# wiring.net
KiCad netlist of a schematic drawn in EAGLE
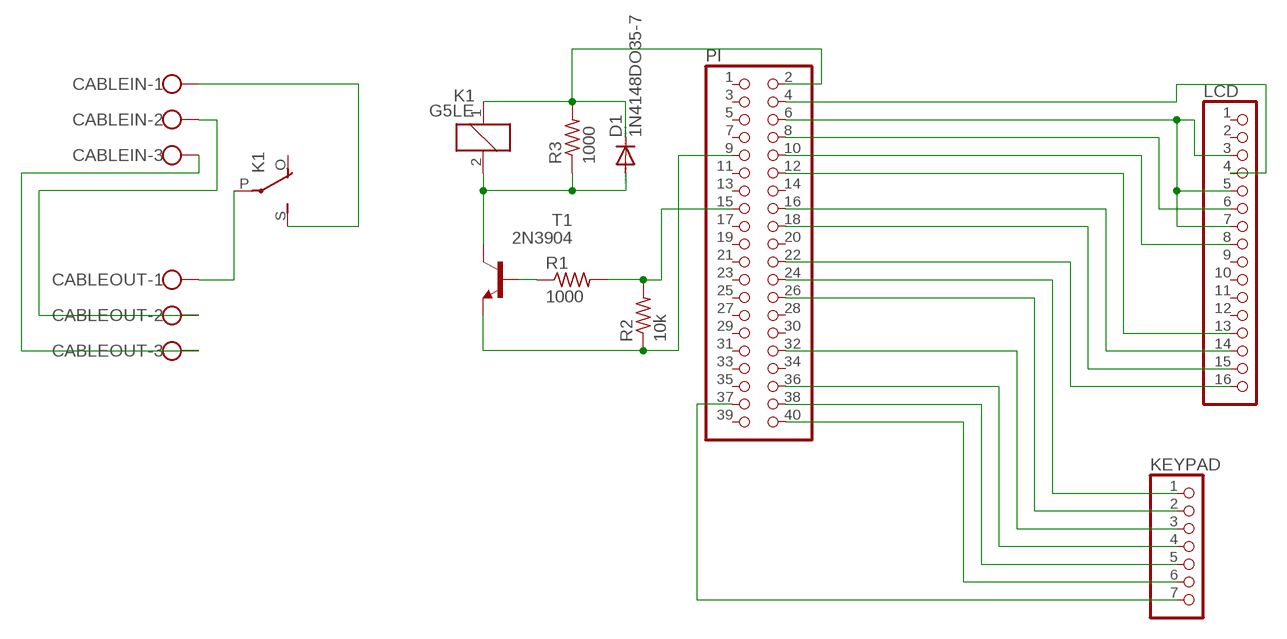
[diagram p0: schematic, sheet 1]

(export (version "E")
  (design (tool "Eeschema 10.0.6"))
  (components
    (comp (ref "CABLEIN")
      (value "W237-103")
      (footprint "eagle-import:W237-103")
      (fields (field (name "MPN") "237-103"))
      (libsource (lib "eagle-import") (part "W237-103"))
    )
    (comp (ref "CABLEOUT")
      (value "W237-103")
      (footprint "eagle-import:W237-103")
      (fields (field (name "MPN") "237-103"))
      (libsource (lib "eagle-import") (part "W237-103"))
    )
    (comp (ref "D1")
      (value "1N4148DO35-7")
      (footprint "eagle-import:DO35-7")
      (libsource (lib "eagle-import") (part "1N4148DO35-7"))
    )
    (comp (ref "K1")
      (value "G5LE")
      (footprint "eagle-import:G5LE")
      (libsource (lib "eagle-import") (part "G5LE"))
    )
    (comp (ref "KEYPAD")
      (value "PINHD-1X7")
      (footprint "eagle-import:1X07")
      (libsource (lib "eagle-import") (part "PINHD-1X7"))
    )
    (comp (ref "LCD")
      (value "PINHD-1X16")
      (footprint "eagle-import:1X16")
      (libsource (lib "eagle-import") (part "PINHD-1X16"))
    )
    (comp (ref "PI")
      (value "PINHD-2X20")
      (footprint "eagle-import:2X20")
      (libsource (lib "eagle-import") (part "PINHD-2X20"))
    )
    (comp (ref "R1")
      (value "1000")
      (footprint "eagle-import:0204_5")
      (libsource (lib "eagle-import") (part "R-US_0204/5"))
    )
    (comp (ref "R2")
      (value "10k")
      (footprint "eagle-import:0204_5")
      (libsource (lib "eagle-import") (part "R-US_0204/5"))
    )
    (comp (ref "R3")
      (value "1000")
      (footprint "eagle-import:0204_5")
      (libsource (lib "eagle-import") (part "R-US_0204/5"))
    )
    (comp (ref "T1")
      (value "2N3904")
      (footprint "eagle-import:TO92")
      (libsource (lib "eagle-import") (part "2N3904"))
    )
  )
  (nets
    (net (code "1") (name "Net-(CABLEINA-KL)") (class "Default")
      (node (ref "CABLEIN") (pin "1") (pinfunction "KL_1") (pintype "passive"))
      (node (ref "K1") (pin "S") (pinfunction "S_S") (pintype "passive"))
    )
    (net (code "2") (name "Net-(CABLEINB-KL)") (class "Default")
      (node (ref "CABLEIN") (pin "2") (pinfunction "KL_2") (pintype "passive"))
      (node (ref "CABLEOUT") (pin "2") (pinfunction "KL_2") (pintype "passive"))
    )
    (net (code "3") (name "Net-(CABLEINC-KL)") (class "Default")
      (node (ref "CABLEIN") (pin "3") (pinfunction "KL_3") (pintype "passive"))
      (node (ref "CABLEOUT") (pin "3") (pinfunction "KL_3") (pintype "passive"))
    )
    (net (code "4") (name "Net-(CABLEOUTA-KL)") (class "Default")
      (node (ref "CABLEOUT") (pin "1") (pinfunction "KL_1") (pintype "passive"))
      (node (ref "K1") (pin "P") (pinfunction "P_P") (pintype "passive"))
    )
    (net (code "5") (name "Net-(D1-PadC)") (class "Default")
      (node (ref "D1") (pin "C") (pinfunction "C_C") (pintype "passive"))
      (node (ref "K1") (pin "1") (pinfunction "1_1") (pintype "passive"))
      (node (ref "PI") (pin "2") (pinfunction "2_2") (pintype "passive"))
      (node (ref "R3") (pin "2") (pinfunction "2_2") (pintype "passive"))
    )
    (net (code "6") (name "Net-(KEYPAD-Pad1)") (class "Default")
      (node (ref "KEYPAD") (pin "1") (pinfunction "1_1") (pintype "passive"))
      (node (ref "PI") (pin "24") (pinfunction "24_24") (pintype "passive"))
    )
    (net (code "7") (name "Net-(KEYPAD-Pad2)") (class "Default")
      (node (ref "KEYPAD") (pin "2") (pinfunction "2_2") (pintype "passive"))
      (node (ref "PI") (pin "26") (pinfunction "26_26") (pintype "passive"))
    )
    (net (code "8") (name "Net-(KEYPAD-Pad3)") (class "Default")
      (node (ref "KEYPAD") (pin "3") (pinfunction "3_3") (pintype "passive"))
      (node (ref "PI") (pin "32") (pinfunction "32_32") (pintype "passive"))
    )
    (net (code "9") (name "Net-(KEYPAD-Pad4)") (class "Default")
      (node (ref "KEYPAD") (pin "4") (pinfunction "4_4") (pintype "passive"))
      (node (ref "PI") (pin "36") (pinfunction "36_36") (pintype "passive"))
    )
    (net (code "10") (name "Net-(KEYPAD-Pad5)") (class "Default")
      (node (ref "KEYPAD") (pin "5") (pinfunction "5_5") (pintype "passive"))
      (node (ref "PI") (pin "38") (pinfunction "38_38") (pintype "passive"))
    )
    (net (code "11") (name "Net-(KEYPAD-Pad6)") (class "Default")
      (node (ref "KEYPAD") (pin "6") (pinfunction "6_6") (pintype "passive"))
      (node (ref "PI") (pin "40") (pinfunction "40_40") (pintype "passive"))
    )
    (net (code "12") (name "Net-(KEYPAD-Pad7)") (class "Default")
      (node (ref "KEYPAD") (pin "7") (pinfunction "7_7") (pintype "passive"))
      (node (ref "PI") (pin "37") (pinfunction "37_37") (pintype "passive"))
    )
    (net (code "13") (name "Net-(LCD-Pad3)") (class "Default")
      (node (ref "LCD") (pin "3") (pinfunction "3_3") (pintype "passive"))
      (node (ref "LCD") (pin "5") (pinfunction "5_5") (pintype "passive"))
      (node (ref "LCD") (pin "7") (pinfunction "7_7") (pintype "passive"))
      (node (ref "PI") (pin "6") (pinfunction "6_6") (pintype "passive"))
    )
    (net (code "14") (name "Net-(LCD-Pad4)") (class "Default")
      (node (ref "LCD") (pin "4") (pinfunction "4_4") (pintype "passive"))
      (node (ref "PI") (pin "4") (pinfunction "4_4") (pintype "passive"))
    )
    (net (code "15") (name "Net-(LCD-Pad6)") (class "Default")
      (node (ref "LCD") (pin "6") (pinfunction "6_6") (pintype "passive"))
      (node (ref "PI") (pin "8") (pinfunction "8_8") (pintype "passive"))
    )
    (net (code "16") (name "Net-(LCD-Pad8)") (class "Default")
      (node (ref "LCD") (pin "8") (pinfunction "8_8") (pintype "passive"))
      (node (ref "PI") (pin "10") (pinfunction "10_10") (pintype "passive"))
    )
    (net (code "17") (name "Net-(LCD-Pad13)") (class "Default")
      (node (ref "LCD") (pin "13") (pinfunction "13_13") (pintype "passive"))
      (node (ref "PI") (pin "12") (pinfunction "12_12") (pintype "passive"))
    )
    (net (code "18") (name "Net-(LCD-Pad14)") (class "Default")
      (node (ref "LCD") (pin "14") (pinfunction "14_14") (pintype "passive"))
      (node (ref "PI") (pin "16") (pinfunction "16_16") (pintype "passive"))
    )
    (net (code "19") (name "Net-(LCD-Pad15)") (class "Default")
      (node (ref "LCD") (pin "15") (pinfunction "15_15") (pintype "passive"))
      (node (ref "PI") (pin "18") (pinfunction "18_18") (pintype "passive"))
    )
    (net (code "20") (name "Net-(LCD-Pad16)") (class "Default")
      (node (ref "LCD") (pin "16") (pinfunction "16_16") (pintype "passive"))
      (node (ref "PI") (pin "22") (pinfunction "22_22") (pintype "passive"))
    )
    (net (code "21") (name "Net-(PI-Pad15)") (class "Default")
      (node (ref "PI") (pin "15") (pinfunction "15_15") (pintype "passive"))
      (node (ref "R1") (pin "2") (pinfunction "2_2") (pintype "passive"))
      (node (ref "R2") (pin "2") (pinfunction "2_2") (pintype "passive"))
    )
    (net (code "22") (name "Net-(T1-B)") (class "Default")
      (node (ref "R1") (pin "1") (pinfunction "1_1") (pintype "passive"))
      (node (ref "T1") (pin "2") (pinfunction "B_2") (pintype "passive"))
    )
    (net (code "23") (name "Net-(T1-C)") (class "Default")
      (node (ref "D1") (pin "A") (pinfunction "A_A") (pintype "passive"))
      (node (ref "K1") (pin "2") (pinfunction "2_2") (pintype "passive"))
      (node (ref "R3") (pin "1") (pinfunction "1_1") (pintype "passive"))
      (node (ref "T1") (pin "1") (pinfunction "C_1") (pintype "passive"))
    )
    (net (code "24") (name "Net-(T1-E)") (class "Default")
      (node (ref "PI") (pin "9") (pinfunction "9_9") (pintype "passive"))
      (node (ref "R2") (pin "1") (pinfunction "1_1") (pintype "passive"))
      (node (ref "T1") (pin "3") (pinfunction "E_3") (pintype "passive"))
    )
    (net (code "25") (name "unconnected-(K1-PadO)") (class "Default")
      (node (ref "K1") (pin "O") (pinfunction "O_O") (pintype "passive"))
    )
    (net (code "26") (name "unconnected-(LCD-Pad1)") (class "Default")
      (node (ref "LCD") (pin "1") (pinfunction "1_1") (pintype "passive"))
    )
    (net (code "27") (name "unconnected-(LCD-Pad2)") (class "Default")
      (node (ref "LCD") (pin "2") (pinfunction "2_2") (pintype "passive"))
    )
    (net (code "28") (name "unconnected-(LCD-Pad9)") (class "Default")
      (node (ref "LCD") (pin "9") (pinfunction "9_9") (pintype "passive"))
    )
    (net (code "29") (name "unconnected-(LCD-Pad10)") (class "Default")
      (node (ref "LCD") (pin "10") (pinfunction "10_10") (pintype "passive"))
    )
    (net (code "30") (name "unconnected-(LCD-Pad11)") (class "Default")
      (node (ref "LCD") (pin "11") (pinfunction "11_11") (pintype "passive"))
    )
    (net (code "31") (name "unconnected-(LCD-Pad12)") (class "Default")
      (node (ref "LCD") (pin "12") (pinfunction "12_12") (pintype "passive"))
    )
    (net (code "32") (name "unconnected-(PI-Pad1)") (class "Default")
      (node (ref "PI") (pin "1") (pinfunction "1_1") (pintype "passive"))
    )
    (net (code "33") (name "unconnected-(PI-Pad3)") (class "Default")
      (node (ref "PI") (pin "3") (pinfunction "3_3") (pintype "passive"))
    )
    (net (code "34") (name "unconnected-(PI-Pad5)") (class "Default")
      (node (ref "PI") (pin "5") (pinfunction "5_5") (pintype "passive"))
    )
    (net (code "35") (name "unconnected-(PI-Pad7)") (class "Default")
      (node (ref "PI") (pin "7") (pinfunction "7_7") (pintype "passive"))
    )
    (net (code "36") (name "unconnected-(PI-Pad11)") (class "Default")
      (node (ref "PI") (pin "11") (pinfunction "11_11") (pintype "passive"))
    )
    (net (code "37") (name "unconnected-(PI-Pad13)") (class "Default")
      (node (ref "PI") (pin "13") (pinfunction "13_13") (pintype "passive"))
    )
    (net (code "38") (name "unconnected-(PI-Pad14)") (class "Default")
      (node (ref "PI") (pin "14") (pinfunction "14_14") (pintype "passive"))
    )
    (net (code "39") (name "unconnected-(PI-Pad17)") (class "Default")
      (node (ref "PI") (pin "17") (pinfunction "17_17") (pintype "passive"))
    )
    (net (code "40") (name "unconnected-(PI-Pad19)") (class "Default")
      (node (ref "PI") (pin "19") (pinfunction "19_19") (pintype "passive"))
    )
    (net (code "41") (name "unconnected-(PI-Pad20)") (class "Default")
      (node (ref "PI") (pin "20") (pinfunction "20_20") (pintype "passive"))
    )
    (net (code "42") (name "unconnected-(PI-Pad21)") (class "Default")
      (node (ref "PI") (pin "21") (pinfunction "21_21") (pintype "passive"))
    )
    (net (code "43") (name "unconnected-(PI-Pad23)") (class "Default")
      (node (ref "PI") (pin "23") (pinfunction "23_23") (pintype "passive"))
    )
    (net (code "44") (name "unconnected-(PI-Pad25)") (class "Default")
      (node (ref "PI") (pin "25") (pinfunction "25_25") (pintype "passive"))
    )
    (net (code "45") (name "unconnected-(PI-Pad27)") (class "Default")
      (node (ref "PI") (pin "27") (pinfunction "27_27") (pintype "passive"))
    )
    (net (code "46") (name "unconnected-(PI-Pad28)") (class "Default")
      (node (ref "PI") (pin "28") (pinfunction "28_28") (pintype "passive"))
    )
    (net (code "47") (name "unconnected-(PI-Pad29)") (class "Default")
      (node (ref "PI") (pin "29") (pinfunction "29_29") (pintype "passive"))
    )
    (net (code "48") (name "unconnected-(PI-Pad30)") (class "Default")
      (node (ref "PI") (pin "30") (pinfunction "30_30") (pintype "passive"))
    )
    (net (code "49") (name "unconnected-(PI-Pad31)") (class "Default")
      (node (ref "PI") (pin "31") (pinfunction "31_31") (pintype "passive"))
    )
    (net (code "50") (name "unconnected-(PI-Pad33)") (class "Default")
      (node (ref "PI") (pin "33") (pinfunction "33_33") (pintype "passive"))
    )
    (net (code "51") (name "unconnected-(PI-Pad34)") (class "Default")
      (node (ref "PI") (pin "34") (pinfunction "34_34") (pintype "passive"))
    )
    (net (code "52") (name "unconnected-(PI-Pad35)") (class "Default")
      (node (ref "PI") (pin "35") (pinfunction "35_35") (pintype "passive"))
    )
    (net (code "53") (name "unconnected-(PI-Pad39)") (class "Default")
      (node (ref "PI") (pin "39") (pinfunction "39_39") (pintype "passive"))
    )
  )
)
